# misc.net
KiCad netlist of a schematic drawn in Altium Designer
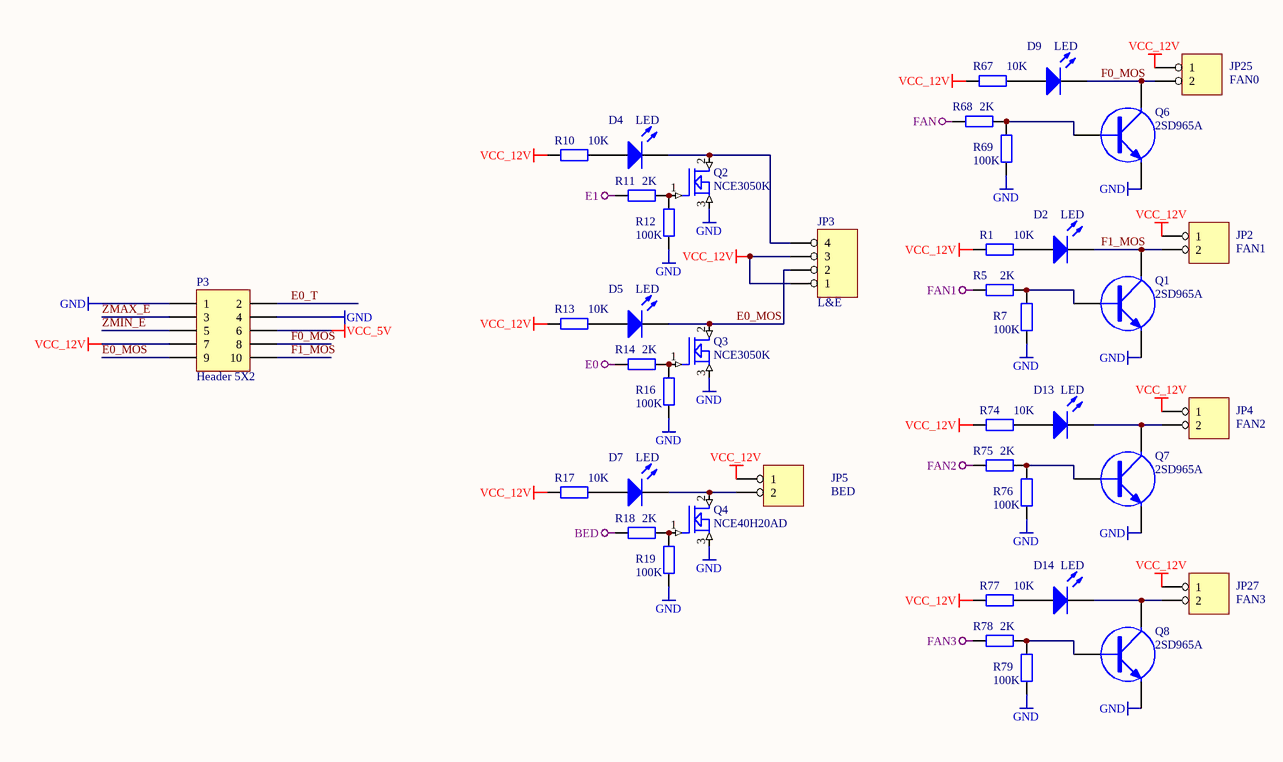
[diagram p0: misc.SchDoc]

(export (version "E")
  (design (tool "Eeschema 10.0.6"))
  (components
    (comp (ref "D2")
      (value "LED")
      (footprint "LED-SMD-0805")
      (description "Typical RED GaAs LED")
      (fields (field (name "PUBLISHER") "Altium Limited"))
      (libsource (lib "Miscellaneous Devices") (part "LED1"))
    )
    (comp (ref "D4")
      (value "LED")
      (footprint "LED-SMD-0805")
      (description "Typical RED GaAs LED")
      (fields (field (name "PUBLISHER") "Altium Limited"))
      (libsource (lib "Miscellaneous Devices") (part "LED1"))
    )
    (comp (ref "D5")
      (value "LED")
      (footprint "LED-SMD-0805")
      (description "Typical RED GaAs LED")
      (fields (field (name "PUBLISHER") "Altium Limited"))
      (libsource (lib "Miscellaneous Devices") (part "LED1"))
    )
    (comp (ref "D7")
      (value "LED")
      (footprint "LED-SMD-0805")
      (description "Typical RED GaAs LED")
      (fields (field (name "PUBLISHER") "Altium Limited"))
      (libsource (lib "Miscellaneous Devices") (part "LED1"))
    )
    (comp (ref "D9")
      (value "LED")
      (footprint "LED-SMD-0805")
      (description "Typical RED GaAs LED")
      (fields (field (name "PUBLISHER") "Altium Limited"))
      (libsource (lib "Miscellaneous Devices") (part "LED1"))
    )
    (comp (ref "D13")
      (value "LED")
      (footprint "LED-SMD-0805")
      (description "Typical RED GaAs LED")
      (fields (field (name "PUBLISHER") "Altium Limited"))
      (libsource (lib "Miscellaneous Devices") (part "LED1"))
    )
    (comp (ref "D14")
      (value "LED")
      (footprint "LED-SMD-0805")
      (description "Typical RED GaAs LED")
      (fields (field (name "PUBLISHER") "Altium Limited"))
      (libsource (lib "Miscellaneous Devices") (part "LED1"))
    )
    (comp (ref "JP2") (value "FAN1") (footprint "XH2.54-2P") (libsource (lib "U_PP SCH") (part "HEADER 2")))
    (comp (ref "JP3")
      (value "L&E")
      (footprint "KF127-4*5.0")
      (description "4 Pin Header")
      (libsource (lib "U_PP SCH") (part "4 HEADER"))
    )
    (comp (ref "JP4") (value "FAN2") (footprint "XH2.54-2P") (libsource (lib "U_PP SCH") (part "HEADER 2")))
    (comp (ref "JP5")
      (value "BED")
      (footprint "POWER JACK-2*5.0")
      (libsource (lib "U_PP SCH") (part "HEADER 2"))
    )
    (comp (ref "JP25") (value "FAN0") (footprint "XH2.54-2P") (libsource (lib "U_PP SCH") (part "HEADER 2")))
    (comp (ref "JP27") (value "FAN3") (footprint "XH2.54-2P") (libsource (lib "U_PP SCH") (part "HEADER 2")))
    (comp (ref "P3")
      (value "Header 5X2")
      (footprint "HX30002-10A")
      (description "Header, 5-Pin, Dual row")
      (fields (field (name "PUBLISHER") "Altium Limited"))
      (libsource (lib "Miscellaneous Connectors") (part "Header 5X2"))
    )
    (comp (ref "Q1")
      (value "2SD965A")
      (footprint "SOT89-3357")
      (description "NPN Transistor")
      (libsource (lib "Miscellaneous Devicespp1") (part "NPN"))
    )
    (comp (ref "Q2")
      (value "NCE3050K")
      (footprint "TO252")
      (libsource (lib "Miscellaneous Devicespp1") (part "NMOS"))
    )
    (comp (ref "Q3")
      (value "NCE3050K")
      (footprint "TO252")
      (libsource (lib "Miscellaneous Devicespp1") (part "NMOS"))
    )
    (comp (ref "Q4")
      (value "NCE40H20AD")
      (footprint "TO263-S")
      (libsource (lib "Miscellaneous Devicespp1") (part "NMOS"))
    )
    (comp (ref "Q6")
      (value "2SD965A")
      (footprint "SOT89-3357")
      (description "NPN Transistor")
      (libsource (lib "Miscellaneous Devicespp1") (part "NPN"))
    )
    (comp (ref "Q7")
      (value "2SD965A")
      (footprint "SOT89-3357")
      (description "NPN Transistor")
      (libsource (lib "Miscellaneous Devicespp1") (part "NPN"))
    )
    (comp (ref "Q8")
      (value "2SD965A")
      (footprint "SOT89-3357")
      (description "NPN Transistor")
      (libsource (lib "Miscellaneous Devicespp1") (part "NPN"))
    )
    (comp (ref "R1")
      (value "10K")
      (footprint "0603(R)")
      (description "Resistor")
      (libsource (lib "*") (part "Res2"))
    )
    (comp (ref "R5")
      (value "2K")
      (footprint "0603(R)")
      (description "1K")
      (fields (field (name "PUBLISHER") "Altium Limited"))
      (libsource (lib "Miscellaneous Devices") (part "Res2"))
    )
    (comp (ref "R7")
      (value "100K")
      (footprint "0603(R)")
      (description "1K")
      (fields (field (name "PUBLISHER") "Altium Limited"))
      (libsource (lib "") (part "Res2_1"))
    )
    (comp (ref "R10")
      (value "10K")
      (footprint "0603(R)")
      (description "Resistor")
      (libsource (lib "*") (part "Res2"))
    )
    (comp (ref "R11")
      (value "2K")
      (footprint "0603(R)")
      (description "1K")
      (fields (field (name "PUBLISHER") "Altium Limited"))
      (libsource (lib "Miscellaneous Devices") (part "Res2"))
    )
    (comp (ref "R12")
      (value "100K")
      (footprint "0603(R)")
      (description "1K")
      (fields (field (name "PUBLISHER") "Altium Limited"))
      (libsource (lib "") (part "Res2_1"))
    )
    (comp (ref "R13")
      (value "10K")
      (footprint "0603(R)")
      (description "Resistor")
      (libsource (lib "*") (part "Res2"))
    )
    (comp (ref "R14")
      (value "2K")
      (footprint "0603(R)")
      (description "1K")
      (fields (field (name "PUBLISHER") "Altium Limited"))
      (libsource (lib "Miscellaneous Devices") (part "Res2"))
    )
    (comp (ref "R16")
      (value "100K")
      (footprint "0603(R)")
      (description "1K")
      (fields (field (name "PUBLISHER") "Altium Limited"))
      (libsource (lib "") (part "Res2_1"))
    )
    (comp (ref "R17")
      (value "10K")
      (footprint "0603(R)")
      (description "Resistor")
      (libsource (lib "*") (part "Res2"))
    )
    (comp (ref "R18")
      (value "2K")
      (footprint "0603(R)")
      (description "1K")
      (fields (field (name "PUBLISHER") "Altium Limited"))
      (libsource (lib "Miscellaneous Devices") (part "Res2"))
    )
    (comp (ref "R19")
      (value "100K")
      (footprint "0603(R)")
      (description "1K")
      (fields (field (name "PUBLISHER") "Altium Limited"))
      (libsource (lib "") (part "Res2_1"))
    )
    (comp (ref "R67")
      (value "10K")
      (footprint "0603(R)")
      (description "Resistor")
      (libsource (lib "*") (part "Res2"))
    )
    (comp (ref "R68")
      (value "2K")
      (footprint "0603(R)")
      (description "1K")
      (fields (field (name "PUBLISHER") "Altium Limited"))
      (libsource (lib "Miscellaneous Devices") (part "Res2"))
    )
    (comp (ref "R69")
      (value "100K")
      (footprint "0603(R)")
      (description "1K")
      (fields (field (name "PUBLISHER") "Altium Limited"))
      (libsource (lib "") (part "Res2_1"))
    )
    (comp (ref "R74")
      (value "10K")
      (footprint "0603(R)")
      (description "Resistor")
      (libsource (lib "*") (part "Res2"))
    )
    (comp (ref "R75")
      (value "2K")
      (footprint "0603(R)")
      (description "1K")
      (fields (field (name "PUBLISHER") "Altium Limited"))
      (libsource (lib "Miscellaneous Devices") (part "Res2"))
    )
    (comp (ref "R76")
      (value "100K")
      (footprint "0603(R)")
      (description "1K")
      (fields (field (name "PUBLISHER") "Altium Limited"))
      (libsource (lib "") (part "Res2_1"))
    )
    (comp (ref "R77")
      (value "10K")
      (footprint "0603(R)")
      (description "Resistor")
      (libsource (lib "*") (part "Res2"))
    )
    (comp (ref "R78")
      (value "2K")
      (footprint "0603(R)")
      (description "1K")
      (fields (field (name "PUBLISHER") "Altium Limited"))
      (libsource (lib "Miscellaneous Devices") (part "Res2"))
    )
    (comp (ref "R79")
      (value "100K")
      (footprint "0603(R)")
      (description "1K")
      (fields (field (name "PUBLISHER") "Altium Limited"))
      (libsource (lib "") (part "Res2_1"))
    )
  )
  (nets
    (net (code "1") (name "/E0_MOS") (class "Default")
      (node (ref "D5") (pin "2") (pinfunction "K_2") (pintype "passive"))
      (node (ref "JP3") (pin "2") (pinfunction "2_2") (pintype "passive"))
      (node (ref "P3") (pin "9") (pinfunction "9_9") (pintype "passive"))
      (node (ref "Q3") (pin "2") (pinfunction "D_2") (pintype "input"))
    )
    (net (code "2") (name "/E0_T") (class "Default")
      (node (ref "P3") (pin "2") (pinfunction "2_2") (pintype "passive"))
    )
    (net (code "3") (name "/F0_MOS") (class "Default")
      (node (ref "D9") (pin "2") (pinfunction "K_2") (pintype "passive"))
      (node (ref "JP25") (pin "2") (pinfunction "2_2") (pintype "passive"))
      (node (ref "P3") (pin "8") (pinfunction "8_8") (pintype "passive"))
      (node (ref "Q6") (pin "3") (pinfunction "C_3") (pintype "passive"))
    )
    (net (code "4") (name "/F1_MOS") (class "Default")
      (node (ref "D2") (pin "2") (pinfunction "K_2") (pintype "passive"))
      (node (ref "JP2") (pin "2") (pinfunction "2_2") (pintype "passive"))
      (node (ref "P3") (pin "10") (pinfunction "10_10") (pintype "passive"))
      (node (ref "Q1") (pin "3") (pinfunction "C_3") (pintype "passive"))
    )
    (net (code "5") (name "/ZMAX_E") (class "Default")
      (node (ref "P3") (pin "3") (pinfunction "3_3") (pintype "passive"))
    )
    (net (code "6") (name "/ZMIN_E") (class "Default")
      (node (ref "P3") (pin "5") (pinfunction "5_5") (pintype "passive"))
    )
    (net (code "7") (name "BED") (class "Default")
      (node (ref "R18") (pin "1") (pinfunction "1_1") (pintype "passive"))
    )
    (net (code "8") (name "E0") (class "Default")
      (node (ref "R14") (pin "1") (pinfunction "1_1") (pintype "passive"))
    )
    (net (code "9") (name "E1") (class "Default")
      (node (ref "R11") (pin "1") (pinfunction "1_1") (pintype "passive"))
    )
    (net (code "10") (name "FAN") (class "Default")
      (node (ref "R68") (pin "1") (pinfunction "1_1") (pintype "passive"))
    )
    (net (code "11") (name "FAN1") (class "Default")
      (node (ref "R5") (pin "1") (pinfunction "1_1") (pintype "passive"))
    )
    (net (code "12") (name "FAN2") (class "Default")
      (node (ref "R75") (pin "1") (pinfunction "1_1") (pintype "passive"))
    )
    (net (code "13") (name "FAN3") (class "Default")
      (node (ref "R78") (pin "1") (pinfunction "1_1") (pintype "passive"))
    )
    (net (code "14") (name "GND") (class "Default")
      (node (ref "P3") (pin "1") (pinfunction "1_1") (pintype "passive"))
      (node (ref "P3") (pin "4") (pinfunction "4_4") (pintype "passive"))
      (node (ref "Q1") (pin "2") (pinfunction "E_2") (pintype "passive"))
      (node (ref "Q2") (pin "3") (pinfunction "S_3") (pintype "input"))
      (node (ref "Q3") (pin "3") (pinfunction "S_3") (pintype "input"))
      (node (ref "Q4") (pin "3") (pinfunction "S_3") (pintype "input"))
      (node (ref "Q6") (pin "2") (pinfunction "E_2") (pintype "passive"))
      (node (ref "Q7") (pin "2") (pinfunction "E_2") (pintype "passive"))
      (node (ref "Q8") (pin "2") (pinfunction "E_2") (pintype "passive"))
      (node (ref "R12") (pin "1") (pinfunction "1_1") (pintype "passive"))
      (node (ref "R16") (pin "1") (pinfunction "1_1") (pintype "passive"))
      (node (ref "R19") (pin "1") (pinfunction "1_1") (pintype "passive"))
      (node (ref "R69") (pin "1") (pinfunction "1_1") (pintype "passive"))
      (node (ref "R7") (pin "1") (pinfunction "1_1") (pintype "passive"))
      (node (ref "R76") (pin "1") (pinfunction "1_1") (pintype "passive"))
      (node (ref "R79") (pin "1") (pinfunction "1_1") (pintype "passive"))
    )
    (net (code "15") (name "Net-(D2-A)") (class "Default")
      (node (ref "D2") (pin "1") (pinfunction "A_1") (pintype "passive"))
      (node (ref "R1") (pin "2") (pinfunction "2_2") (pintype "passive"))
    )
    (net (code "16") (name "Net-(D4-A)") (class "Default")
      (node (ref "D4") (pin "1") (pinfunction "A_1") (pintype "passive"))
      (node (ref "R10") (pin "2") (pinfunction "2_2") (pintype "passive"))
    )
    (net (code "17") (name "Net-(D4-K)") (class "Default")
      (node (ref "D4") (pin "2") (pinfunction "K_2") (pintype "passive"))
      (node (ref "JP3") (pin "4") (pinfunction "4_4") (pintype "passive"))
      (node (ref "Q2") (pin "2") (pinfunction "D_2") (pintype "input"))
    )
    (net (code "18") (name "Net-(D5-A)") (class "Default")
      (node (ref "D5") (pin "1") (pinfunction "A_1") (pintype "passive"))
      (node (ref "R13") (pin "2") (pinfunction "2_2") (pintype "passive"))
    )
    (net (code "19") (name "Net-(D7-A)") (class "Default")
      (node (ref "D7") (pin "1") (pinfunction "A_1") (pintype "passive"))
      (node (ref "R17") (pin "2") (pinfunction "2_2") (pintype "passive"))
    )
    (net (code "20") (name "Net-(D7-K)") (class "Default")
      (node (ref "D7") (pin "2") (pinfunction "K_2") (pintype "passive"))
      (node (ref "JP5") (pin "2") (pinfunction "2_2") (pintype "passive"))
      (node (ref "Q4") (pin "2") (pinfunction "D_2") (pintype "input"))
    )
    (net (code "21") (name "Net-(D9-A)") (class "Default")
      (node (ref "D9") (pin "1") (pinfunction "A_1") (pintype "passive"))
      (node (ref "R67") (pin "2") (pinfunction "2_2") (pintype "passive"))
    )
    (net (code "22") (name "Net-(D13-A)") (class "Default")
      (node (ref "D13") (pin "1") (pinfunction "A_1") (pintype "passive"))
      (node (ref "R74") (pin "2") (pinfunction "2_2") (pintype "passive"))
    )
    (net (code "23") (name "Net-(D13-K)") (class "Default")
      (node (ref "D13") (pin "2") (pinfunction "K_2") (pintype "passive"))
      (node (ref "JP4") (pin "2") (pinfunction "2_2") (pintype "passive"))
      (node (ref "Q7") (pin "3") (pinfunction "C_3") (pintype "passive"))
    )
    (net (code "24") (name "Net-(D14-A)") (class "Default")
      (node (ref "D14") (pin "1") (pinfunction "A_1") (pintype "passive"))
      (node (ref "R77") (pin "2") (pinfunction "2_2") (pintype "passive"))
    )
    (net (code "25") (name "Net-(D14-K)") (class "Default")
      (node (ref "D14") (pin "2") (pinfunction "K_2") (pintype "passive"))
      (node (ref "JP27") (pin "2") (pinfunction "2_2") (pintype "passive"))
      (node (ref "Q8") (pin "3") (pinfunction "C_3") (pintype "passive"))
    )
    (net (code "26") (name "Net-(Q1-B)") (class "Default")
      (node (ref "Q1") (pin "1") (pinfunction "B_1") (pintype "passive"))
      (node (ref "R5") (pin "2") (pinfunction "2_2") (pintype "passive"))
      (node (ref "R7") (pin "2") (pinfunction "2_2") (pintype "passive"))
    )
    (net (code "27") (name "Net-(Q2-G)") (class "Default")
      (node (ref "Q2") (pin "1") (pinfunction "G_1") (pintype "input"))
      (node (ref "R11") (pin "2") (pinfunction "2_2") (pintype "passive"))
      (node (ref "R12") (pin "2") (pinfunction "2_2") (pintype "passive"))
    )
    (net (code "28") (name "Net-(Q3-G)") (class "Default")
      (node (ref "Q3") (pin "1") (pinfunction "G_1") (pintype "input"))
      (node (ref "R14") (pin "2") (pinfunction "2_2") (pintype "passive"))
      (node (ref "R16") (pin "2") (pinfunction "2_2") (pintype "passive"))
    )
    (net (code "29") (name "Net-(Q4-G)") (class "Default")
      (node (ref "Q4") (pin "1") (pinfunction "G_1") (pintype "input"))
      (node (ref "R18") (pin "2") (pinfunction "2_2") (pintype "passive"))
      (node (ref "R19") (pin "2") (pinfunction "2_2") (pintype "passive"))
    )
    (net (code "30") (name "Net-(Q6-B)") (class "Default")
      (node (ref "Q6") (pin "1") (pinfunction "B_1") (pintype "passive"))
      (node (ref "R68") (pin "2") (pinfunction "2_2") (pintype "passive"))
      (node (ref "R69") (pin "2") (pinfunction "2_2") (pintype "passive"))
    )
    (net (code "31") (name "Net-(Q7-B)") (class "Default")
      (node (ref "Q7") (pin "1") (pinfunction "B_1") (pintype "passive"))
      (node (ref "R75") (pin "2") (pinfunction "2_2") (pintype "passive"))
      (node (ref "R76") (pin "2") (pinfunction "2_2") (pintype "passive"))
    )
    (net (code "32") (name "Net-(Q8-B)") (class "Default")
      (node (ref "Q8") (pin "1") (pinfunction "B_1") (pintype "passive"))
      (node (ref "R78") (pin "2") (pinfunction "2_2") (pintype "passive"))
      (node (ref "R79") (pin "2") (pinfunction "2_2") (pintype "passive"))
    )
    (net (code "33") (name "VCC_5V") (class "Default")
      (node (ref "P3") (pin "6") (pinfunction "6_6") (pintype "passive"))
    )
    (net (code "34") (name "VCC_12V") (class "Default")
      (node (ref "JP2") (pin "1") (pinfunction "1_1") (pintype "passive"))
      (node (ref "JP25") (pin "1") (pinfunction "1_1") (pintype "passive"))
      (node (ref "JP27") (pin "1") (pinfunction "1_1") (pintype "passive"))
      (node (ref "JP3") (pin "1") (pinfunction "1_1") (pintype "passive"))
      (node (ref "JP3") (pin "3") (pinfunction "3_3") (pintype "passive"))
      (node (ref "JP4") (pin "1") (pinfunction "1_1") (pintype "passive"))
      (node (ref "JP5") (pin "1") (pinfunction "1_1") (pintype "passive"))
      (node (ref "P3") (pin "7") (pinfunction "7_7") (pintype "passive"))
      (node (ref "R1") (pin "1") (pinfunction "1_1") (pintype "passive"))
      (node (ref "R10") (pin "1") (pinfunction "1_1") (pintype "passive"))
      (node (ref "R13") (pin "1") (pinfunction "1_1") (pintype "passive"))
      (node (ref "R17") (pin "1") (pinfunction "1_1") (pintype "passive"))
      (node (ref "R67") (pin "1") (pinfunction "1_1") (pintype "passive"))
      (node (ref "R74") (pin "1") (pinfunction "1_1") (pintype "passive"))
      (node (ref "R77") (pin "1") (pinfunction "1_1") (pintype "passive"))
    )
  )
)
